# uNav4x4r1_PTH.net
KiCad netlist of a schematic drawn in EAGLE
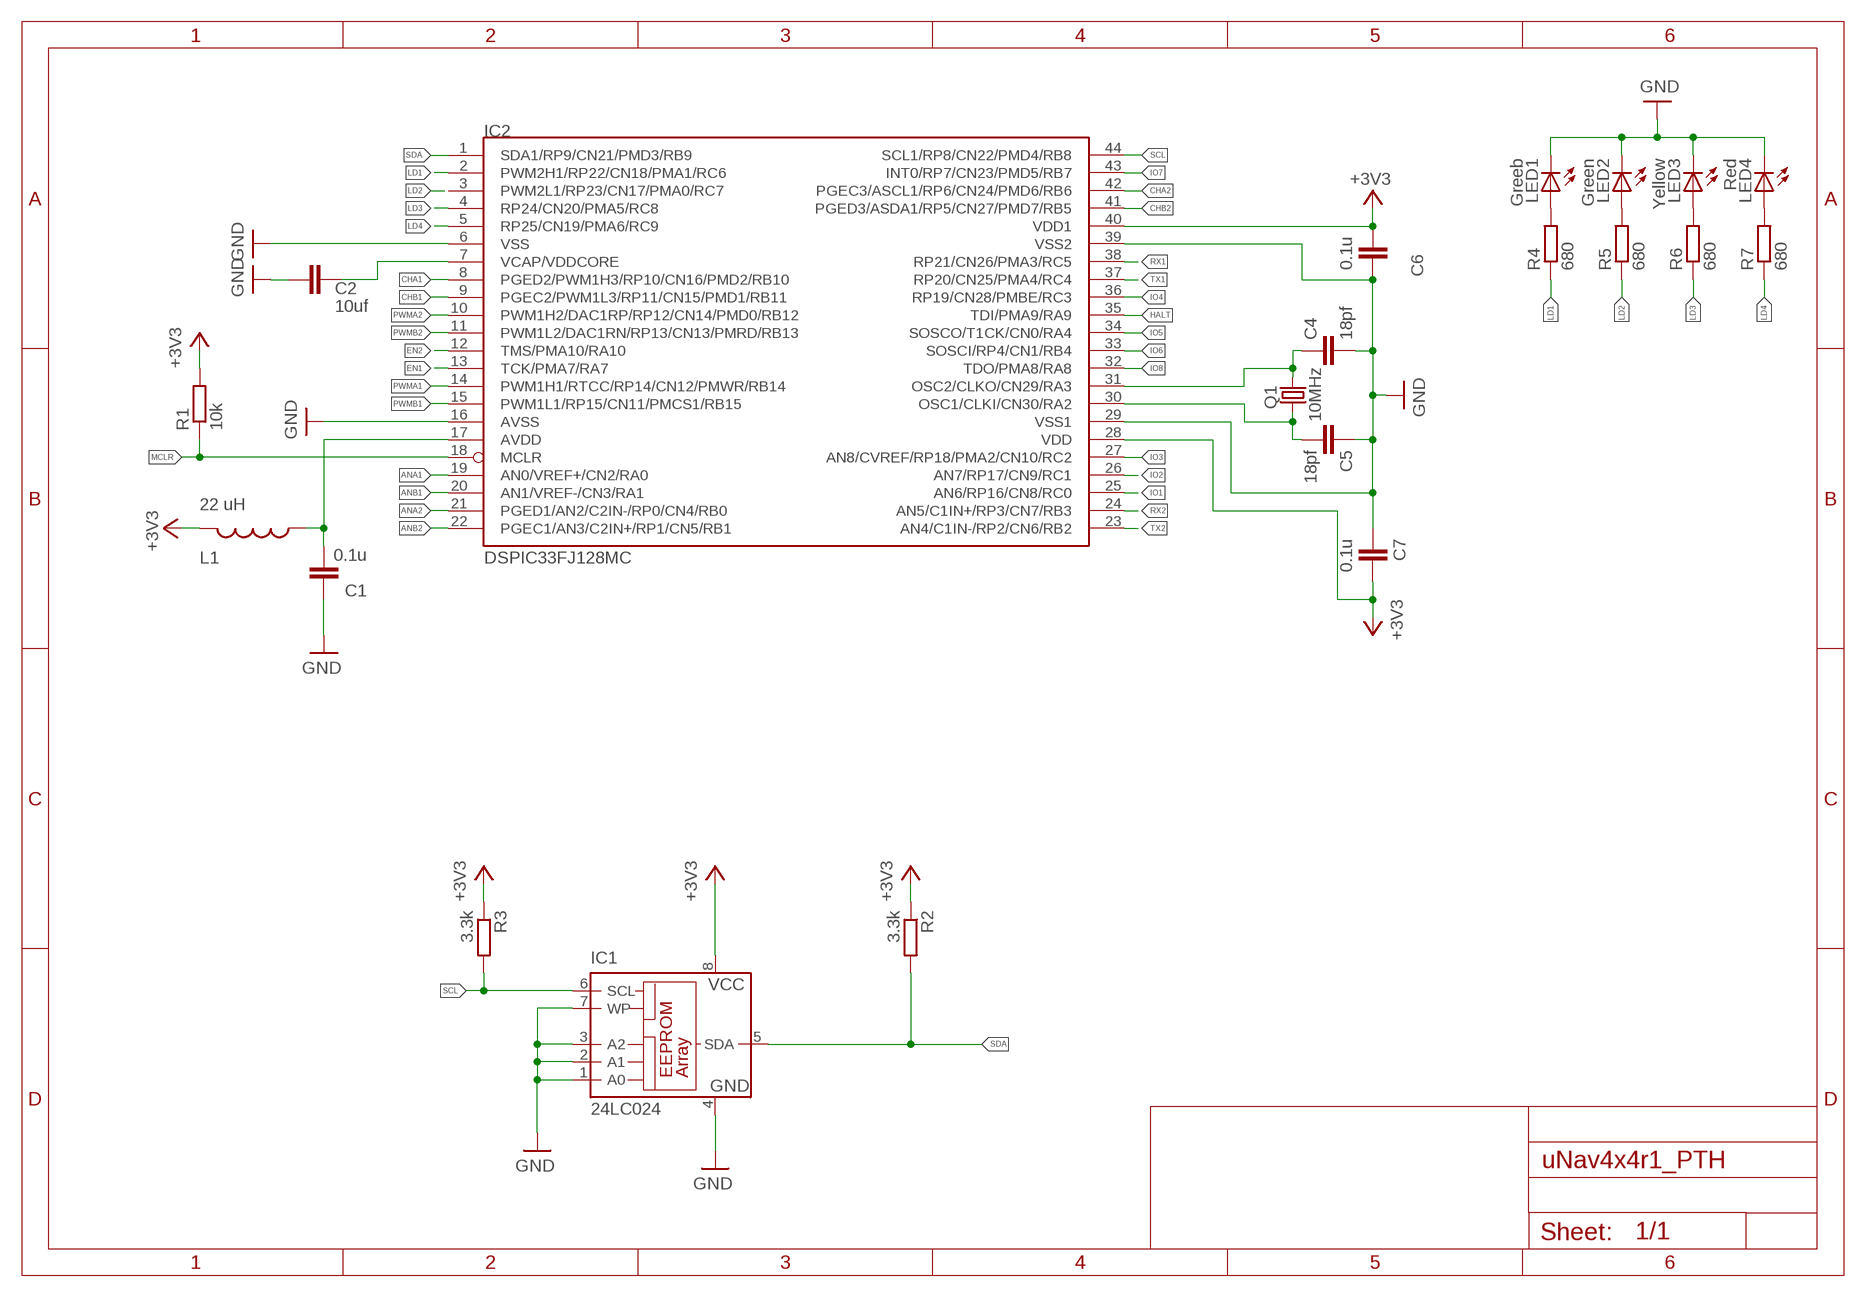
[diagram p0: schematic, sheet 1, part 1 of 2]
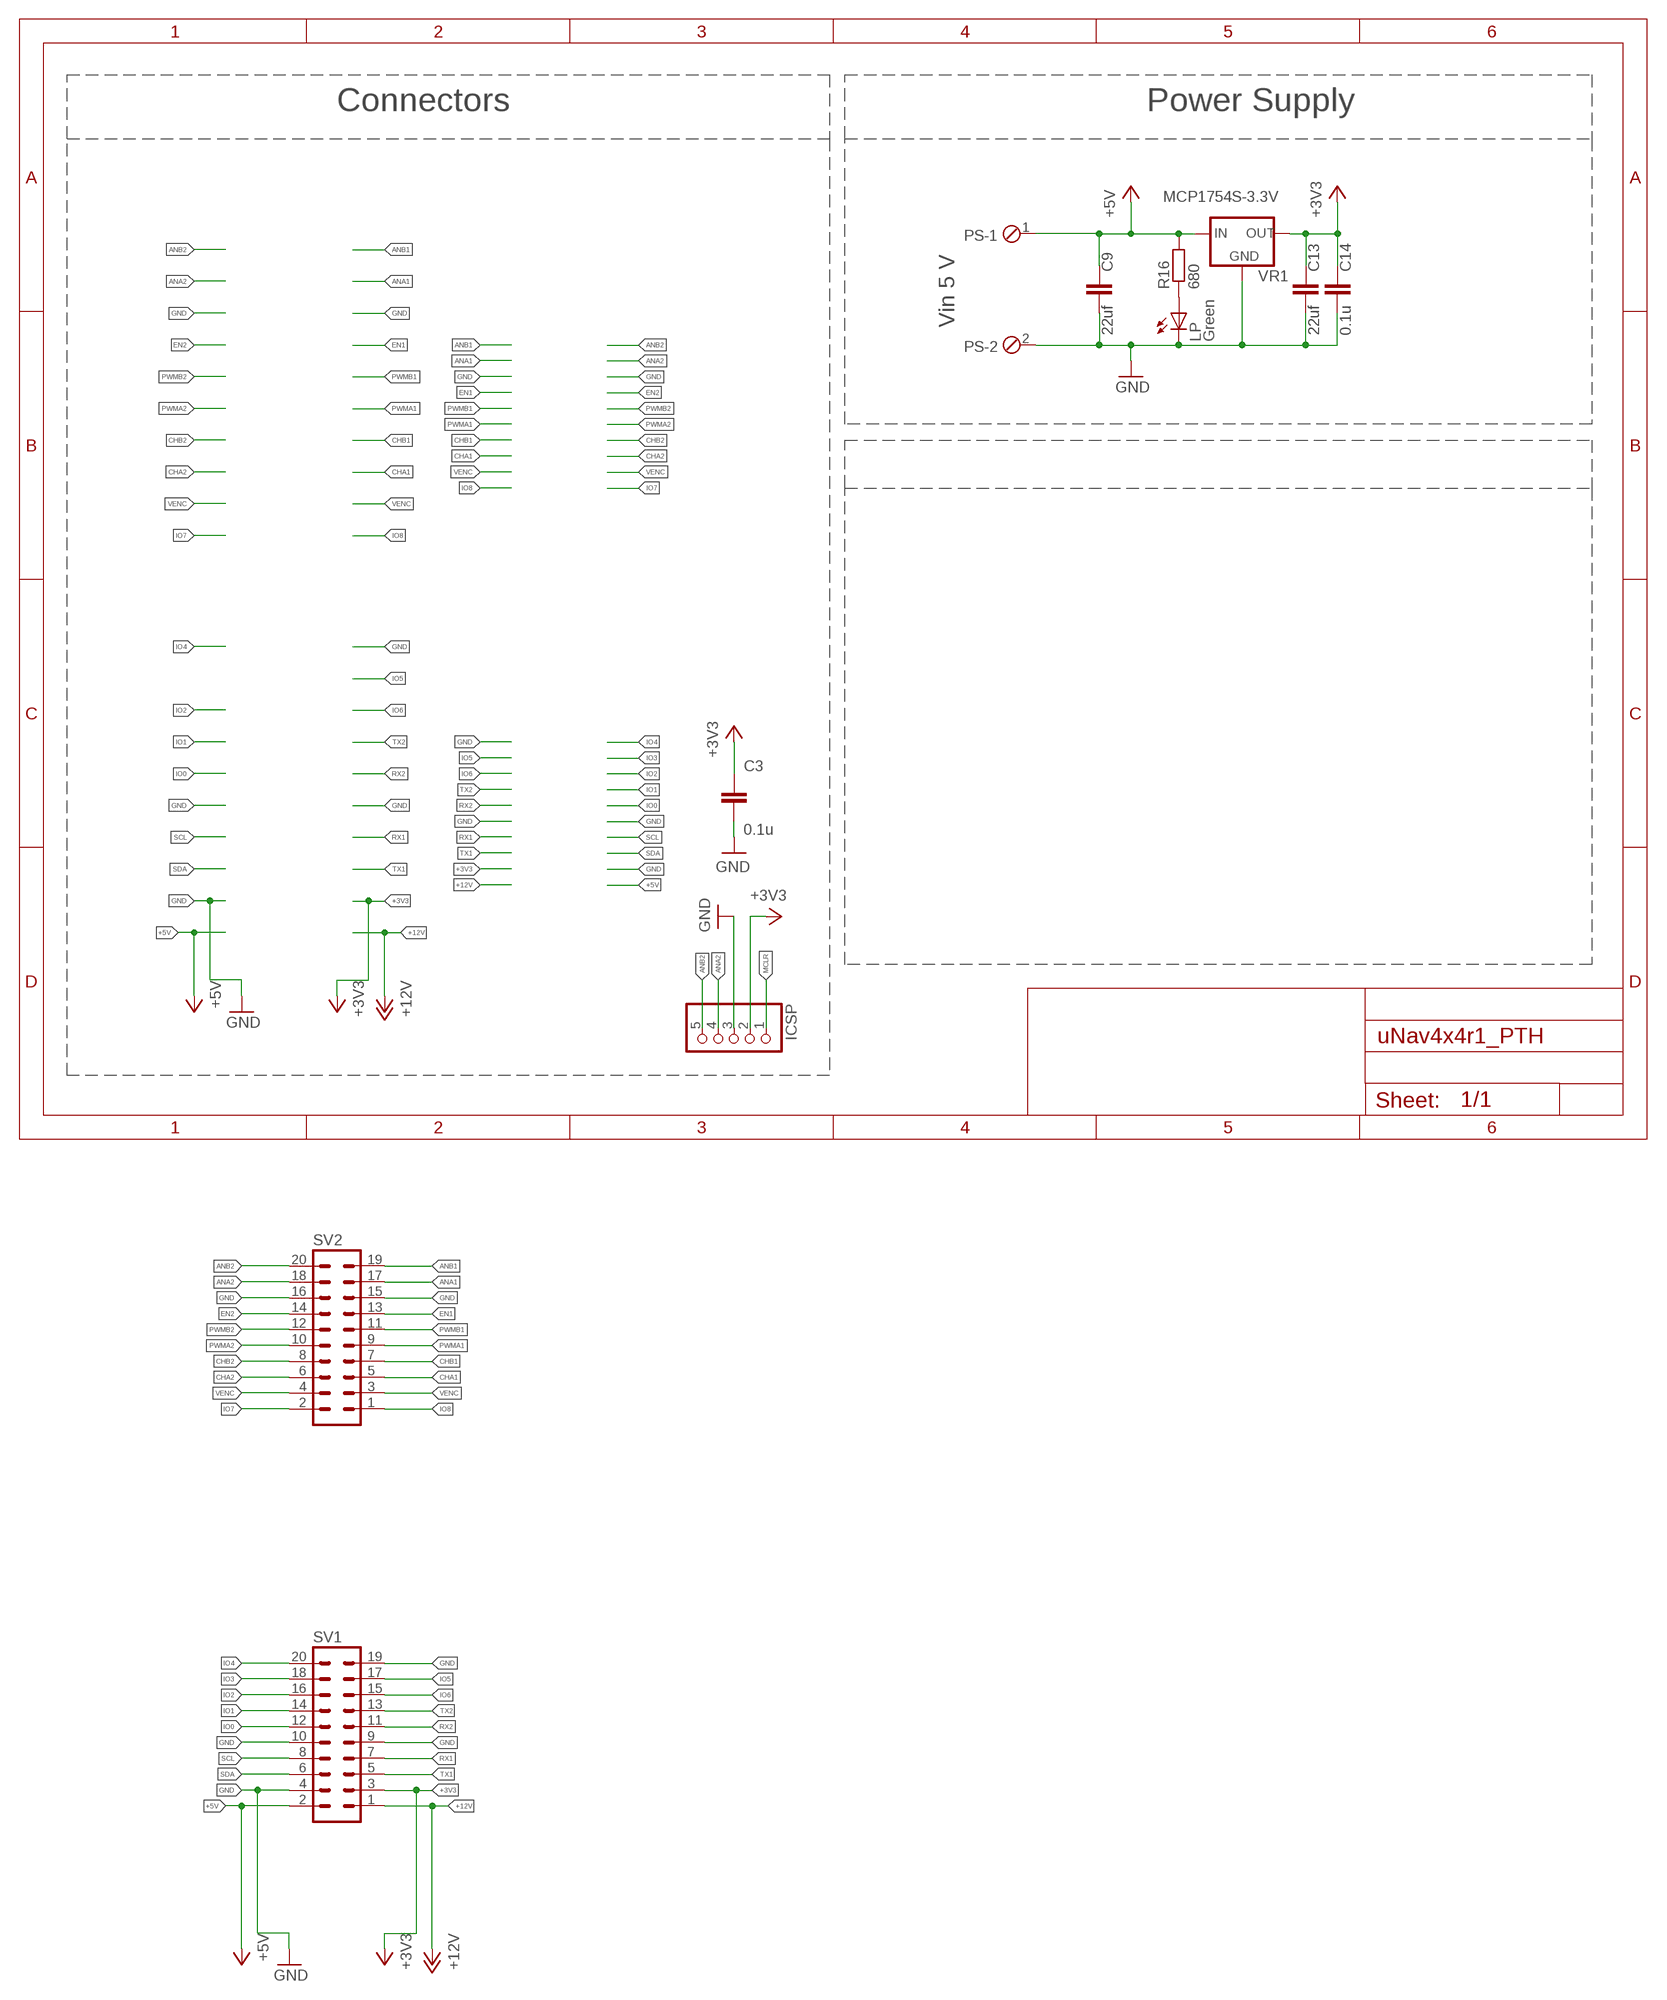
[diagram p1: schematic, sheet 1, part 2 of 2]

(export (version "E")
  (design (tool "Eeschema 10.0.6"))
  (components
    (comp (ref "C1")
      (value "0.1u")
      (footprint "eagle-import:C0603")
      (libsource (lib "eagle-import") (part "C-EUC0603"))
    )
    (comp (ref "C2")
      (value "10uf")
      (footprint "eagle-import:C1206")
      (libsource (lib "eagle-import") (part "C-EUC1206"))
    )
    (comp (ref "C3")
      (value "0.1u")
      (footprint "eagle-import:C0603")
      (libsource (lib "eagle-import") (part "C-EUC0603"))
    )
    (comp (ref "C4")
      (value "18pf")
      (footprint "eagle-import:C0603")
      (libsource (lib "eagle-import") (part "C-EUC0603"))
    )
    (comp (ref "C5")
      (value "18pf")
      (footprint "eagle-import:C0603")
      (libsource (lib "eagle-import") (part "C-EUC0603"))
    )
    (comp (ref "C6")
      (value "0.1u")
      (footprint "eagle-import:C0603")
      (libsource (lib "eagle-import") (part "C-EUC0603"))
    )
    (comp (ref "C7")
      (value "0.1u")
      (footprint "eagle-import:C0603")
      (libsource (lib "eagle-import") (part "C-EUC0603"))
    )
    (comp (ref "C9")
      (value "22uf")
      (footprint "eagle-import:C1206")
      (libsource (lib "eagle-import") (part "C-EUC1206"))
    )
    (comp (ref "C13")
      (value "22uf")
      (footprint "eagle-import:C1206")
      (libsource (lib "eagle-import") (part "C-EUC1206"))
    )
    (comp (ref "C14")
      (value "0.1u")
      (footprint "eagle-import:C0603")
      (libsource (lib "eagle-import") (part "C-EUC0603"))
    )
    (comp (ref "IC1")
      (value "24LC024")
      (footprint "eagle-import:SO-08M")
      (fields (field (name "MF") "MICROCHIP") (field (name "MPN") "24AA01-I/SN"))
      (libsource (lib "eagle-import") (part "24SMAA01"))
    )
    (comp (ref "IC2")
      (value "DSPIC33FJ128MC")
      (footprint "eagle-import:TQFP44")
      (libsource (lib "eagle-import") (part "DSPIC33FJ128MC804-PT"))
    )
    (comp (ref "ICSP")
      (value "PINHD-1X05_2.54-S")
      (footprint "eagle-import:1X05-S")
      (libsource (lib "eagle-import") (part "PINHD-1X05_2.54-S"))
    )
    (comp (ref "L1")
      (value "22 uH")
      (footprint "eagle-import:0805")
      (libsource (lib "eagle-import") (part "INDUCTOR0805"))
    )
    (comp (ref "LED1")
      (value "Greeb")
      (footprint "eagle-import:CHIPLED_0805")
      (libsource (lib "eagle-import") (part "LEDCHIPLED_0805"))
    )
    (comp (ref "LED2")
      (value "Green")
      (footprint "eagle-import:CHIPLED_0805")
      (libsource (lib "eagle-import") (part "LEDCHIPLED_0805"))
    )
    (comp (ref "LED3")
      (value "Yellow")
      (footprint "eagle-import:CHIPLED_0805")
      (libsource (lib "eagle-import") (part "LEDCHIPLED_0805"))
    )
    (comp (ref "LED4")
      (value "Red")
      (footprint "eagle-import:CHIPLED_0805")
      (libsource (lib "eagle-import") (part "LEDCHIPLED_0805"))
    )
    (comp (ref "LP")
      (value "Green")
      (footprint "eagle-import:CHIPLED_0805")
      (libsource (lib "eagle-import") (part "LEDCHIPLED_0805"))
    )
    (comp (ref "PS")
      (value "MPT2")
      (footprint "eagle-import:2POL254")
      (libsource (lib "eagle-import") (part "MPT2"))
    )
    (comp (ref "Q1")
      (value "10MHz")
      (footprint "eagle-import:HC49U-V")
      (libsource (lib "eagle-import") (part "CRYSTALHC49U-V"))
    )
    (comp (ref "R1")
      (value "10k")
      (footprint "eagle-import:R0603")
      (libsource (lib "eagle-import") (part "R-EU_R0603"))
    )
    (comp (ref "R2")
      (value "3.3k")
      (footprint "eagle-import:R0603")
      (libsource (lib "eagle-import") (part "R-EU_R0603"))
    )
    (comp (ref "R3")
      (value "3.3k")
      (footprint "eagle-import:R0603")
      (libsource (lib "eagle-import") (part "R-EU_R0603"))
    )
    (comp (ref "R4")
      (value "680")
      (footprint "eagle-import:R0603")
      (libsource (lib "eagle-import") (part "R-EU_R0603"))
    )
    (comp (ref "R5")
      (value "680")
      (footprint "eagle-import:R0603")
      (libsource (lib "eagle-import") (part "R-EU_R0603"))
    )
    (comp (ref "R6")
      (value "680")
      (footprint "eagle-import:R0603")
      (libsource (lib "eagle-import") (part "R-EU_R0603"))
    )
    (comp (ref "R7")
      (value "680")
      (footprint "eagle-import:R0603")
      (libsource (lib "eagle-import") (part "R-EU_R0603"))
    )
    (comp (ref "R16")
      (value "680")
      (footprint "eagle-import:R0603")
      (libsource (lib "eagle-import") (part "R-EU_R0603"))
    )
    (comp (ref "SV1")
      (value "MA10-2")
      (footprint "eagle-import:MA10-2")
      (libsource (lib "eagle-import") (part "MA10-2"))
    )
    (comp (ref "SV2")
      (value "MA10-2")
      (footprint "eagle-import:MA10-2")
      (fields (field (name "OC_FARNELL") "unknown") (field (name "OC_NEWARK") "unknown"))
      (libsource (lib "eagle-import") (part "MA10-2"))
    )
    (comp (ref "VR1")
      (value "MCP1754S-3.3V")
      (footprint "eagle-import:SOT89")
      (libsource (lib "eagle-import") (part "MCP1754S"))
    )
  )
  (nets
    (net (code "1") (name "+3V3") (class "Default")
      (node (ref "C13") (pin "1") (pinfunction "1_1") (pintype "passive"))
      (node (ref "C14") (pin "1") (pinfunction "1_1") (pintype "passive"))
      (node (ref "C3") (pin "1") (pinfunction "1_1") (pintype "passive"))
      (node (ref "C6") (pin "2") (pinfunction "2_2") (pintype "passive"))
      (node (ref "C7") (pin "1") (pinfunction "1_1") (pintype "passive"))
      (node (ref "IC1") (pin "8") (pinfunction "VCC_8") (pintype "power_in"))
      (node (ref "IC2") (pin "28") (pinfunction "VDD_28") (pintype "power_in"))
      (node (ref "IC2") (pin "40") (pinfunction "VDD1_40") (pintype "power_in"))
      (node (ref "ICSP") (pin "2") (pinfunction "2_2") (pintype "passive"))
      (node (ref "L1") (pin "2") (pinfunction "2_2") (pintype "passive"))
      (node (ref "R1") (pin "2") (pinfunction "2_2") (pintype "passive"))
      (node (ref "R2") (pin "1") (pinfunction "1_1") (pintype "passive"))
      (node (ref "R3") (pin "1") (pinfunction "1_1") (pintype "passive"))
      (node (ref "SV1") (pin "3") (pinfunction "3_3") (pintype "passive"))
      (node (ref "VR1") (pin "3") (pinfunction "OUT_3") (pintype "passive"))
    )
    (net (code "2") (name "+5V") (class "Default")
      (node (ref "C9") (pin "1") (pinfunction "1_1") (pintype "passive"))
      (node (ref "PS") (pin "1") (pinfunction "1_1") (pintype "passive"))
      (node (ref "R16") (pin "2") (pinfunction "2_2") (pintype "passive"))
      (node (ref "SV1") (pin "2") (pinfunction "2_2") (pintype "passive"))
      (node (ref "VR1") (pin "1") (pinfunction "IN_1") (pintype "input"))
    )
    (net (code "3") (name "+12V") (class "Default")
      (node (ref "SV1") (pin "1") (pinfunction "1_1") (pintype "passive"))
    )
    (net (code "4") (name "ANA1") (class "Default")
      (node (ref "IC2") (pin "19") (pinfunction "AN0/VREF+/CN2/RA0_19") (pintype "bidirectional"))
      (node (ref "SV2") (pin "17") (pinfunction "17_17") (pintype "passive"))
    )
    (net (code "5") (name "ANA2") (class "Default")
      (node (ref "IC2") (pin "21") (pinfunction "PGED1/AN2/C2IN-/RP0/CN4/RB0_21") (pintype "bidirectional"))
      (node (ref "ICSP") (pin "4") (pinfunction "4_4") (pintype "passive"))
      (node (ref "SV2") (pin "18") (pinfunction "18_18") (pintype "passive"))
    )
    (net (code "6") (name "ANB1") (class "Default")
      (node (ref "IC2") (pin "20") (pinfunction "AN1/VREF-/CN3/RA1_20") (pintype "bidirectional"))
      (node (ref "SV2") (pin "19") (pinfunction "19_19") (pintype "passive"))
    )
    (net (code "7") (name "ANB2") (class "Default")
      (node (ref "IC2") (pin "22") (pinfunction "PGEC1/AN3/C2IN+/RP1/CN5/RB1_22") (pintype "bidirectional"))
      (node (ref "ICSP") (pin "5") (pinfunction "5_5") (pintype "passive"))
      (node (ref "SV2") (pin "20") (pinfunction "20_20") (pintype "passive"))
    )
    (net (code "8") (name "CHA1") (class "Default")
      (node (ref "IC2") (pin "8") (pinfunction "PGED2/PWM1H3/RP10/CN16/PMD2/RB10_8") (pintype "bidirectional"))
      (node (ref "SV2") (pin "5") (pinfunction "5_5") (pintype "passive"))
    )
    (net (code "9") (name "CHA2") (class "Default")
      (node (ref "IC2") (pin "42") (pinfunction "PGEC3/ASCL1/RP6/CN24/PMD6/RB6_42") (pintype "bidirectional"))
      (node (ref "SV2") (pin "6") (pinfunction "6_6") (pintype "passive"))
    )
    (net (code "10") (name "CHB1") (class "Default")
      (node (ref "IC2") (pin "9") (pinfunction "PGEC2/PWM1L3/RP11/CN15/PMD1/RB11_9") (pintype "bidirectional"))
      (node (ref "SV2") (pin "7") (pinfunction "7_7") (pintype "passive"))
    )
    (net (code "11") (name "CHB2") (class "Default")
      (node (ref "IC2") (pin "41") (pinfunction "PGED3/ASDA1/RP5/CN27/PMD7/RB5_41") (pintype "bidirectional"))
      (node (ref "SV2") (pin "8") (pinfunction "8_8") (pintype "passive"))
    )
    (net (code "12") (name "EN1") (class "Default")
      (node (ref "IC2") (pin "13") (pinfunction "TCK/PMA7/RA7_13") (pintype "bidirectional"))
      (node (ref "SV2") (pin "13") (pinfunction "13_13") (pintype "passive"))
    )
    (net (code "13") (name "EN2") (class "Default")
      (node (ref "IC2") (pin "12") (pinfunction "TMS/PMA10/RA10_12") (pintype "bidirectional"))
      (node (ref "SV2") (pin "14") (pinfunction "14_14") (pintype "passive"))
    )
    (net (code "14") (name "GND") (class "Default")
      (node (ref "C1") (pin "1") (pinfunction "1_1") (pintype "passive"))
      (node (ref "C13") (pin "2") (pinfunction "2_2") (pintype "passive"))
      (node (ref "C14") (pin "2") (pinfunction "2_2") (pintype "passive"))
      (node (ref "C2") (pin "2") (pinfunction "2_2") (pintype "passive"))
      (node (ref "C3") (pin "2") (pinfunction "2_2") (pintype "passive"))
      (node (ref "C4") (pin "2") (pinfunction "2_2") (pintype "passive"))
      (node (ref "C5") (pin "1") (pinfunction "1_1") (pintype "passive"))
      (node (ref "C6") (pin "1") (pinfunction "1_1") (pintype "passive"))
      (node (ref "C7") (pin "2") (pinfunction "2_2") (pintype "passive"))
      (node (ref "C9") (pin "2") (pinfunction "2_2") (pintype "passive"))
      (node (ref "IC1") (pin "1") (pinfunction "A0_1") (pintype "input"))
      (node (ref "IC1") (pin "2") (pinfunction "A1_2") (pintype "input"))
      (node (ref "IC1") (pin "3") (pinfunction "A2_3") (pintype "input"))
      (node (ref "IC1") (pin "4") (pinfunction "GND_4") (pintype "power_in"))
      (node (ref "IC1") (pin "7") (pinfunction "WP_7") (pintype "input"))
      (node (ref "IC2") (pin "16") (pinfunction "AVSS_16") (pintype "power_in"))
      (node (ref "IC2") (pin "29") (pinfunction "VSS1_29") (pintype "power_in"))
      (node (ref "IC2") (pin "39") (pinfunction "VSS2_39") (pintype "power_in"))
      (node (ref "IC2") (pin "6") (pinfunction "VSS_6") (pintype "power_in"))
      (node (ref "ICSP") (pin "3") (pinfunction "3_3") (pintype "passive"))
      (node (ref "LED1") (pin "C") (pinfunction "C_C") (pintype "passive"))
      (node (ref "LED2") (pin "C") (pinfunction "C_C") (pintype "passive"))
      (node (ref "LED3") (pin "C") (pinfunction "C_C") (pintype "passive"))
      (node (ref "LED4") (pin "C") (pinfunction "C_C") (pintype "passive"))
      (node (ref "LP") (pin "C") (pinfunction "C_C") (pintype "passive"))
      (node (ref "PS") (pin "2") (pinfunction "1_2") (pintype "passive"))
      (node (ref "SV1") (pin "10") (pinfunction "10_10") (pintype "passive"))
      (node (ref "SV1") (pin "19") (pinfunction "19_19") (pintype "passive"))
      (node (ref "SV1") (pin "4") (pinfunction "4_4") (pintype "passive"))
      (node (ref "SV1") (pin "9") (pinfunction "9_9") (pintype "passive"))
      (node (ref "SV2") (pin "15") (pinfunction "15_15") (pintype "passive"))
      (node (ref "SV2") (pin "16") (pinfunction "16_16") (pintype "passive"))
      (node (ref "VR1") (pin "2") (pinfunction "GND_2") (pintype "input"))
      (node (ref "VR1") (pin "4") (pinfunction "GND_4") (pintype "input"))
    )
    (net (code "15") (name "HALT") (class "Default")
      (node (ref "IC2") (pin "35") (pinfunction "TDI/PMA9/RA9_35") (pintype "bidirectional"))
    )
    (net (code "16") (name "IO0") (class "Default")
      (node (ref "SV1") (pin "12") (pinfunction "12_12") (pintype "passive"))
    )
    (net (code "17") (name "IO1") (class "Default")
      (node (ref "IC2") (pin "25") (pinfunction "AN6/RP16/CN8/RC0_25") (pintype "bidirectional"))
      (node (ref "SV1") (pin "14") (pinfunction "14_14") (pintype "passive"))
    )
    (net (code "18") (name "IO2") (class "Default")
      (node (ref "IC2") (pin "26") (pinfunction "AN7/RP17/CN9/RC1_26") (pintype "bidirectional"))
      (node (ref "SV1") (pin "16") (pinfunction "16_16") (pintype "passive"))
    )
    (net (code "19") (name "IO3") (class "Default")
      (node (ref "IC2") (pin "27") (pinfunction "AN8/CVREF/RP18/PMA2/CN10/RC2_27") (pintype "bidirectional"))
      (node (ref "SV1") (pin "18") (pinfunction "18_18") (pintype "passive"))
    )
    (net (code "20") (name "IO4") (class "Default")
      (node (ref "IC2") (pin "36") (pinfunction "RP19/CN28/PMBE/RC3_36") (pintype "bidirectional"))
      (node (ref "SV1") (pin "20") (pinfunction "20_20") (pintype "passive"))
    )
    (net (code "21") (name "IO5") (class "Default")
      (node (ref "IC2") (pin "34") (pinfunction "SOSCO/T1CK/CN0/RA4_34") (pintype "bidirectional"))
      (node (ref "SV1") (pin "17") (pinfunction "17_17") (pintype "passive"))
    )
    (net (code "22") (name "IO6") (class "Default")
      (node (ref "IC2") (pin "33") (pinfunction "SOSCI/RP4/CN1/RB4_33") (pintype "bidirectional"))
      (node (ref "SV1") (pin "15") (pinfunction "15_15") (pintype "passive"))
    )
    (net (code "23") (name "IO7") (class "Default")
      (node (ref "IC2") (pin "43") (pinfunction "INT0/RP7/CN23/PMD5/RB7_43") (pintype "bidirectional"))
      (node (ref "SV2") (pin "2") (pinfunction "2_2") (pintype "passive"))
    )
    (net (code "24") (name "IO8") (class "Default")
      (node (ref "IC2") (pin "32") (pinfunction "TDO/PMA8/RA8_32") (pintype "bidirectional"))
      (node (ref "SV2") (pin "1") (pinfunction "1_1") (pintype "passive"))
    )
    (net (code "25") (name "LD1") (class "Default")
      (node (ref "IC2") (pin "2") (pinfunction "PWM2H1/RP22/CN18/PMA1/RC6_2") (pintype "bidirectional"))
      (node (ref "R4") (pin "1") (pinfunction "1_1") (pintype "passive"))
    )
    (net (code "26") (name "LD2") (class "Default")
      (node (ref "IC2") (pin "3") (pinfunction "PWM2L1/RP23/CN17/PMA0/RC7_3") (pintype "bidirectional"))
      (node (ref "R5") (pin "1") (pinfunction "1_1") (pintype "passive"))
    )
    (net (code "27") (name "LD3") (class "Default")
      (node (ref "IC2") (pin "4") (pinfunction "RP24/CN20/PMA5/RC8_4") (pintype "bidirectional"))
      (node (ref "R6") (pin "1") (pinfunction "1_1") (pintype "passive"))
    )
    (net (code "28") (name "LD4") (class "Default")
      (node (ref "IC2") (pin "5") (pinfunction "RP25/CN19/PMA6/RC9_5") (pintype "bidirectional"))
      (node (ref "R7") (pin "1") (pinfunction "1_1") (pintype "passive"))
    )
    (net (code "29") (name "MCLR") (class "Default")
      (node (ref "IC2") (pin "18") (pinfunction "MCLR_18") (pintype "input"))
      (node (ref "ICSP") (pin "1") (pinfunction "1_1") (pintype "passive"))
      (node (ref "R1") (pin "1") (pinfunction "1_1") (pintype "passive"))
    )
    (net (code "30") (name "Net-(IC2-AVDD)") (class "Default")
      (node (ref "C1") (pin "2") (pinfunction "2_2") (pintype "passive"))
      (node (ref "IC2") (pin "17") (pinfunction "AVDD_17") (pintype "power_in"))
      (node (ref "L1") (pin "1") (pinfunction "1_1") (pintype "passive"))
    )
    (net (code "31") (name "Net-(IC2-OSC1{slash}CLKI{slash}CN30{slash}RA2)") (class "Default")
      (node (ref "C5") (pin "2") (pinfunction "2_2") (pintype "passive"))
      (node (ref "IC2") (pin "30") (pinfunction "OSC1/CLKI/CN30/RA2_30") (pintype "bidirectional"))
      (node (ref "Q1") (pin "1") (pinfunction "1_1") (pintype "passive"))
    )
    (net (code "32") (name "Net-(IC2-OSC2{slash}CLKO{slash}CN29{slash}RA3)") (class "Default")
      (node (ref "C4") (pin "1") (pinfunction "1_1") (pintype "passive"))
      (node (ref "IC2") (pin "31") (pinfunction "OSC2/CLKO/CN29/RA3_31") (pintype "bidirectional"))
      (node (ref "Q1") (pin "2") (pinfunction "2_2") (pintype "passive"))
    )
    (net (code "33") (name "Net-(IC2-VCAP{slash}VDDCORE)") (class "Default")
      (node (ref "C2") (pin "1") (pinfunction "1_1") (pintype "passive"))
      (node (ref "IC2") (pin "7") (pinfunction "VCAP/VDDCORE_7") (pintype "power_in"))
    )
    (net (code "34") (name "Net-(LED1-PadA)") (class "Default")
      (node (ref "LED1") (pin "A") (pinfunction "A_A") (pintype "passive"))
      (node (ref "R4") (pin "2") (pinfunction "2_2") (pintype "passive"))
    )
    (net (code "35") (name "Net-(LED2-PadA)") (class "Default")
      (node (ref "LED2") (pin "A") (pinfunction "A_A") (pintype "passive"))
      (node (ref "R5") (pin "2") (pinfunction "2_2") (pintype "passive"))
    )
    (net (code "36") (name "Net-(LED3-PadA)") (class "Default")
      (node (ref "LED3") (pin "A") (pinfunction "A_A") (pintype "passive"))
      (node (ref "R6") (pin "2") (pinfunction "2_2") (pintype "passive"))
    )
    (net (code "37") (name "Net-(LED4-PadA)") (class "Default")
      (node (ref "LED4") (pin "A") (pinfunction "A_A") (pintype "passive"))
      (node (ref "R7") (pin "2") (pinfunction "2_2") (pintype "passive"))
    )
    (net (code "38") (name "Net-(LP-PadA)") (class "Default")
      (node (ref "LP") (pin "A") (pinfunction "A_A") (pintype "passive"))
      (node (ref "R16") (pin "1") (pinfunction "1_1") (pintype "passive"))
    )
    (net (code "39") (name "PWMA1") (class "Default")
      (node (ref "IC2") (pin "14") (pinfunction "PWM1H1/RTCC/RP14/CN12/PMWR/RB14_14") (pintype "bidirectional"))
      (node (ref "SV2") (pin "9") (pinfunction "9_9") (pintype "passive"))
    )
    (net (code "40") (name "PWMA2") (class "Default")
      (node (ref "IC2") (pin "10") (pinfunction "PWM1H2/DAC1RP/RP12/CN14/PMD0/RB12_10") (pintype "bidirectional"))
      (node (ref "SV2") (pin "10") (pinfunction "10_10") (pintype "passive"))
    )
    (net (code "41") (name "PWMB1") (class "Default")
      (node (ref "IC2") (pin "15") (pinfunction "PWM1L1/RP15/CN11/PMCS1/RB15_15") (pintype "bidirectional"))
      (node (ref "SV2") (pin "11") (pinfunction "11_11") (pintype "passive"))
    )
    (net (code "42") (name "PWMB2") (class "Default")
      (node (ref "IC2") (pin "11") (pinfunction "PWM1L2/DAC1RN/RP13/CN13/PMRD/RB13_11") (pintype "bidirectional"))
      (node (ref "SV2") (pin "12") (pinfunction "12_12") (pintype "passive"))
    )
    (net (code "43") (name "RX1") (class "Default")
      (node (ref "IC2") (pin "38") (pinfunction "RP21/CN26/PMA3/RC5_38") (pintype "bidirectional"))
      (node (ref "SV1") (pin "7") (pinfunction "7_7") (pintype "passive"))
    )
    (net (code "44") (name "RX2") (class "Default")
      (node (ref "IC2") (pin "24") (pinfunction "AN5/C1IN+/RP3/CN7/RB3_24") (pintype "bidirectional"))
      (node (ref "SV1") (pin "11") (pinfunction "11_11") (pintype "passive"))
    )
    (net (code "45") (name "SCL") (class "Default")
      (node (ref "IC1") (pin "6") (pinfunction "SCL_6") (pintype "input"))
      (node (ref "IC2") (pin "44") (pinfunction "SCL1/RP8/CN22/PMD4/RB8_44") (pintype "bidirectional"))
      (node (ref "R3") (pin "2") (pinfunction "2_2") (pintype "passive"))
      (node (ref "SV1") (pin "8") (pinfunction "8_8") (pintype "passive"))
    )
    (net (code "46") (name "SDA") (class "Default")
      (node (ref "IC1") (pin "5") (pinfunction "SDA_5") (pintype "bidirectional"))
      (node (ref "IC2") (pin "1") (pinfunction "SDA1/RP9/CN21/PMD3/RB9_1") (pintype "bidirectional"))
      (node (ref "R2") (pin "2") (pinfunction "2_2") (pintype "passive"))
      (node (ref "SV1") (pin "6") (pinfunction "6_6") (pintype "passive"))
    )
    (net (code "47") (name "TX1") (class "Default")
      (node (ref "IC2") (pin "37") (pinfunction "RP20/CN25/PMA4/RC4_37") (pintype "bidirectional"))
      (node (ref "SV1") (pin "5") (pinfunction "5_5") (pintype "passive"))
    )
    (net (code "48") (name "TX2") (class "Default")
      (node (ref "IC2") (pin "23") (pinfunction "AN4/C1IN-/RP2/CN6/RB2_23") (pintype "bidirectional"))
      (node (ref "SV1") (pin "13") (pinfunction "13_13") (pintype "passive"))
    )
    (net (code "49") (name "VENC") (class "Default")
      (node (ref "SV2") (pin "3") (pinfunction "3_3") (pintype "passive"))
      (node (ref "SV2") (pin "4") (pinfunction "4_4") (pintype "passive"))
    )
  )
)
